# dengenn.net
KiCad netlist of a schematic drawn in EAGLE
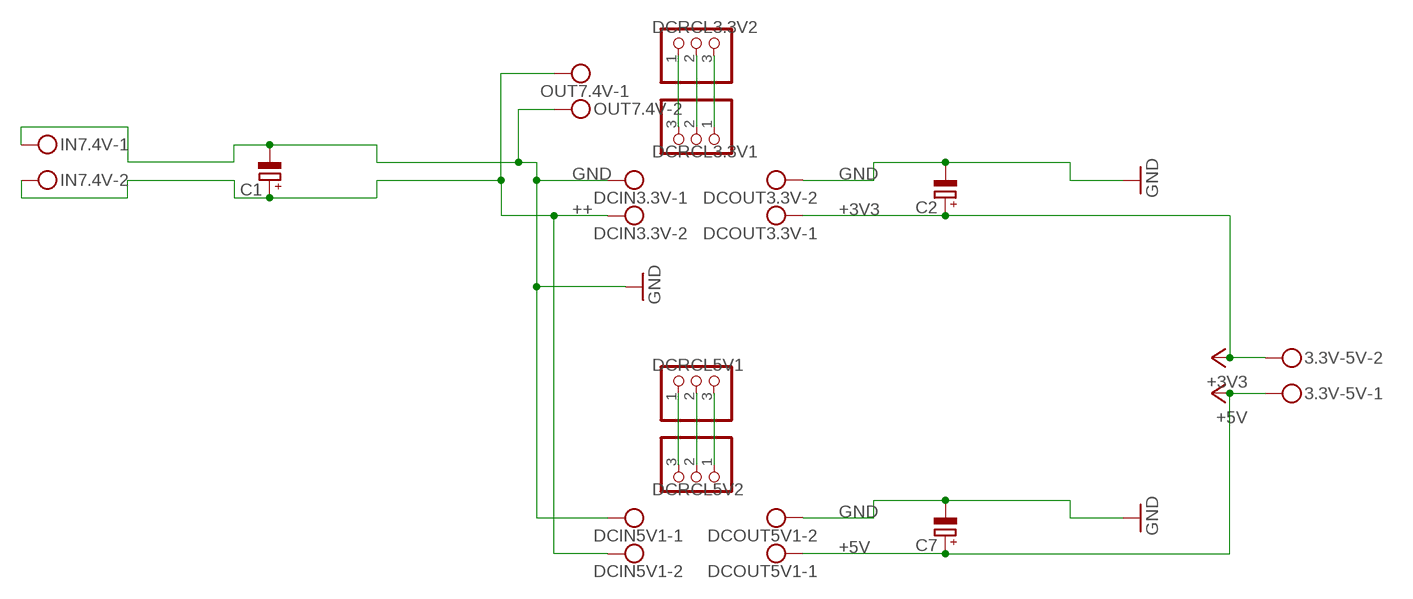
[diagram p0: schematic, sheet 1]

(export (version "E")
  (design (tool "Eeschema 10.0.6"))
  (components
    (comp (ref "3.3V-5V")
      (value "MKDSN1,5/2-5,08")
      (footprint "eagle-import:MKDSN1,5_2-5,08")
      (libsource (lib "eagle-import") (part "MKDSN1,5/2-5,08"))
    )
    (comp (ref "C1")
      (value "CPOL-EUE5-10.5")
      (footprint "eagle-import:E5-10,5")
      (libsource (lib "eagle-import") (part "CPOL-EUE5-10.5"))
    )
    (comp (ref "C2")
      (value "CPOL-EUE5-10.5")
      (footprint "eagle-import:E5-10,5")
      (libsource (lib "eagle-import") (part "CPOL-EUE5-10.5"))
    )
    (comp (ref "C7")
      (value "CPOL-EUE5-10.5")
      (footprint "eagle-import:E5-10,5")
      (libsource (lib "eagle-import") (part "CPOL-EUE5-10.5"))
    )
    (comp (ref "DCIN3.3V")
      (value "MKDSN1,5/2-5,08")
      (footprint "eagle-import:MKDSN1,5_2-5,08")
      (libsource (lib "eagle-import") (part "MKDSN1,5/2-5,08"))
    )
    (comp (ref "DCIN5V1")
      (value "MKDSN1,5/2-5,08")
      (footprint "eagle-import:MKDSN1,5_2-5,08")
      (libsource (lib "eagle-import") (part "MKDSN1,5/2-5,08"))
    )
    (comp (ref "DCOUT3.3V")
      (value "MKDSN1,5/2-5,08")
      (footprint "eagle-import:MKDSN1,5_2-5,08")
      (libsource (lib "eagle-import") (part "MKDSN1,5/2-5,08"))
    )
    (comp (ref "DCOUT5V1")
      (value "MKDSN1,5/2-5,08")
      (footprint "eagle-import:MKDSN1,5_2-5,08")
      (libsource (lib "eagle-import") (part "MKDSN1,5/2-5,08"))
    )
    (comp (ref "DCRCL3.3V1")
      (value "PINHD-1X3")
      (footprint "eagle-import:1X03")
      (libsource (lib "eagle-import") (part "PINHD-1X3"))
    )
    (comp (ref "DCRCL3.3V2")
      (value "PINHD-1X3")
      (footprint "eagle-import:1X03")
      (libsource (lib "eagle-import") (part "PINHD-1X3"))
    )
    (comp (ref "DCRCL5V1")
      (value "PINHD-1X3")
      (footprint "eagle-import:1X03")
      (libsource (lib "eagle-import") (part "PINHD-1X3"))
    )
    (comp (ref "DCRCL5V2")
      (value "PINHD-1X3")
      (footprint "eagle-import:1X03")
      (libsource (lib "eagle-import") (part "PINHD-1X3"))
    )
    (comp (ref "IN7.4V")
      (value "MKDSN1,5/2-5,08")
      (footprint "eagle-import:MKDSN1,5_2-5,08")
      (libsource (lib "eagle-import") (part "MKDSN1,5/2-5,08"))
    )
    (comp (ref "OUT7.4V")
      (value "MKDSN1,5/2-5,08")
      (footprint "eagle-import:MKDSN1,5_2-5,08")
      (libsource (lib "eagle-import") (part "MKDSN1,5/2-5,08"))
    )
  )
  (nets
    (net (code "1") (name "+3V3") (class "Default")
      (node (ref "3.3V-5V") (pin "2") (pinfunction "KL_2") (pintype "passive"))
      (node (ref "C2") (pin "+") (pinfunction "+_+") (pintype "passive"))
      (node (ref "DCOUT3.3V") (pin "1") (pinfunction "KL_1") (pintype "passive"))
    )
    (net (code "2") (name "+5V") (class "Default")
      (node (ref "3.3V-5V") (pin "1") (pinfunction "KL_1") (pintype "passive"))
      (node (ref "C7") (pin "+") (pinfunction "+_+") (pintype "passive"))
      (node (ref "DCOUT5V1") (pin "1") (pinfunction "KL_1") (pintype "passive"))
    )
    (net (code "3") (name "/++") (class "Default")
      (node (ref "C1") (pin "+") (pinfunction "+_+") (pintype "passive"))
      (node (ref "DCIN3.3V") (pin "2") (pinfunction "KL_2") (pintype "passive"))
      (node (ref "DCIN5V1") (pin "2") (pinfunction "KL_2") (pintype "passive"))
      (node (ref "IN7.4V") (pin "2") (pinfunction "KL_2") (pintype "passive"))
      (node (ref "OUT7.4V") (pin "1") (pinfunction "KL_1") (pintype "passive"))
    )
    (net (code "4") (name "GND") (class "Default")
      (node (ref "C1") (pin "-") (pinfunction "-_-") (pintype "passive"))
      (node (ref "C2") (pin "-") (pinfunction "-_-") (pintype "passive"))
      (node (ref "C7") (pin "-") (pinfunction "-_-") (pintype "passive"))
      (node (ref "DCIN3.3V") (pin "1") (pinfunction "KL_1") (pintype "passive"))
      (node (ref "DCIN5V1") (pin "1") (pinfunction "KL_1") (pintype "passive"))
      (node (ref "DCOUT3.3V") (pin "2") (pinfunction "KL_2") (pintype "passive"))
      (node (ref "DCOUT5V1") (pin "2") (pinfunction "KL_2") (pintype "passive"))
      (node (ref "IN7.4V") (pin "1") (pinfunction "KL_1") (pintype "passive"))
      (node (ref "OUT7.4V") (pin "2") (pinfunction "KL_2") (pintype "passive"))
    )
    (net (code "5") (name "Net-(DCRCL3.3V1-Pad1)") (class "Default")
      (node (ref "DCRCL3.3V1") (pin "1") (pinfunction "1_1") (pintype "passive"))
      (node (ref "DCRCL3.3V2") (pin "3") (pinfunction "3_3") (pintype "passive"))
    )
    (net (code "6") (name "Net-(DCRCL3.3V1-Pad2)") (class "Default")
      (node (ref "DCRCL3.3V1") (pin "2") (pinfunction "2_2") (pintype "passive"))
      (node (ref "DCRCL3.3V2") (pin "2") (pinfunction "2_2") (pintype "passive"))
    )
    (net (code "7") (name "Net-(DCRCL3.3V1-Pad3)") (class "Default")
      (node (ref "DCRCL3.3V1") (pin "3") (pinfunction "3_3") (pintype "passive"))
      (node (ref "DCRCL3.3V2") (pin "1") (pinfunction "1_1") (pintype "passive"))
    )
    (net (code "8") (name "Net-(DCRCL5V1-Pad1)") (class "Default")
      (node (ref "DCRCL5V1") (pin "1") (pinfunction "1_1") (pintype "passive"))
      (node (ref "DCRCL5V2") (pin "3") (pinfunction "3_3") (pintype "passive"))
    )
    (net (code "9") (name "Net-(DCRCL5V1-Pad2)") (class "Default")
      (node (ref "DCRCL5V1") (pin "2") (pinfunction "2_2") (pintype "passive"))
      (node (ref "DCRCL5V2") (pin "2") (pinfunction "2_2") (pintype "passive"))
    )
    (net (code "10") (name "Net-(DCRCL5V1-Pad3)") (class "Default")
      (node (ref "DCRCL5V1") (pin "3") (pinfunction "3_3") (pintype "passive"))
      (node (ref "DCRCL5V2") (pin "1") (pinfunction "1_1") (pintype "passive"))
    )
  )
)
